# Bus_V3_1.net
KiCad netlist of a schematic drawn in EAGLE
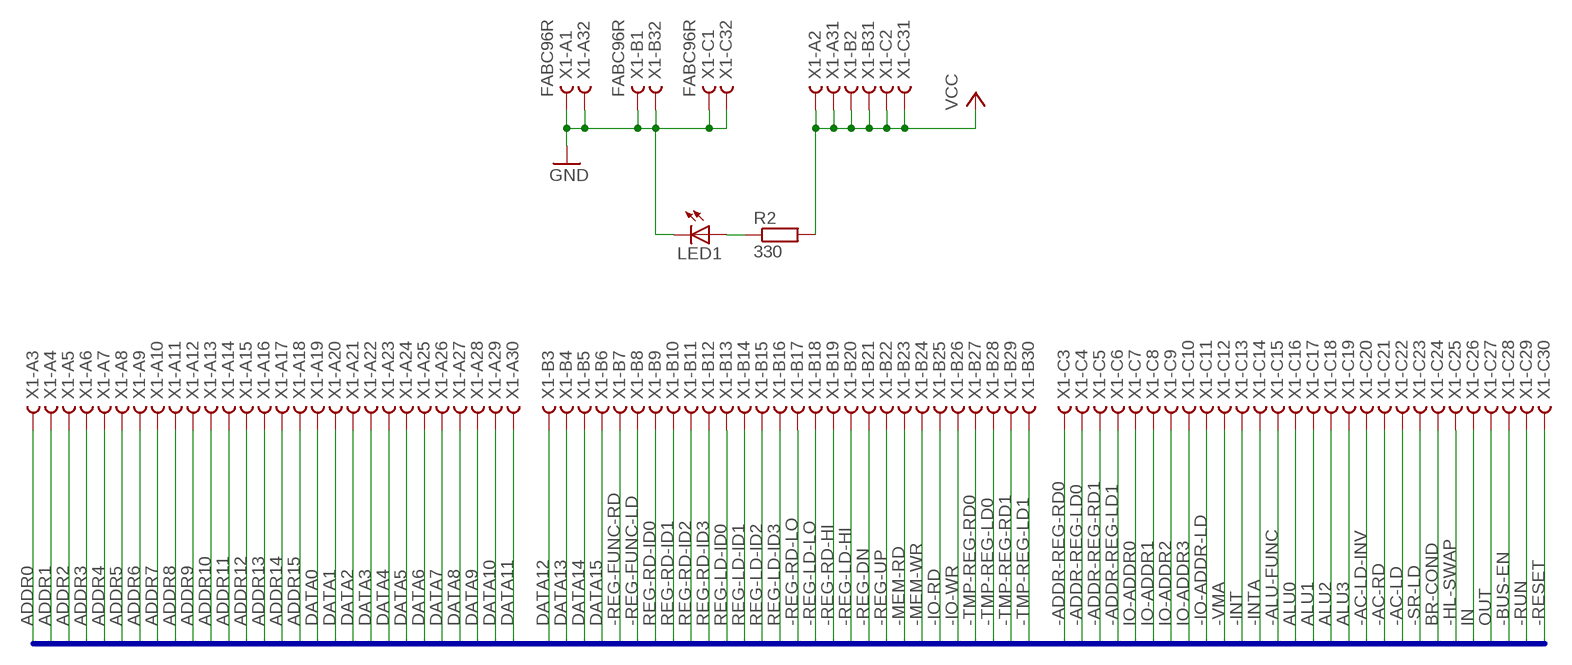
[diagram p0: schematic, sheet 1]

(export (version "E")
  (design (tool "Eeschema 10.0.6"))
  (components
    (comp (ref "LED1")
      (value "LED5MM")
      (footprint "eagle-import:LED5MM")
      (libsource (lib "eagle-import") (part "LED5MM"))
    )
    (comp (ref "R2")
      (value "330")
      (footprint "eagle-import:0207_10")
      (libsource (lib "eagle-import") (part "R0207/10"))
    )
    (comp (ref "X1")
      (value "FABC96R")
      (footprint "eagle-import:FABC96R")
      (libsource (lib "eagle-import") (part "FABC96R"))
    )
  )
  (nets
    (net (code "1") (name "/-AC-LD") (class "Default")
      (node (ref "X1") (pin "C22") (pinfunction "B_C22") (pintype "passive"))
    )
    (net (code "2") (name "/-AC-LD-INV") (class "Default")
      (node (ref "X1") (pin "C20") (pinfunction "B_C20") (pintype "passive"))
    )
    (net (code "3") (name "/-AC-RD") (class "Default")
      (node (ref "X1") (pin "C21") (pinfunction "B_C21") (pintype "passive"))
    )
    (net (code "4") (name "/-ADDR-REG-LD0") (class "Default")
      (node (ref "X1") (pin "C4") (pinfunction "B_C4") (pintype "passive"))
    )
    (net (code "5") (name "/-ADDR-REG-LD1") (class "Default")
      (node (ref "X1") (pin "C6") (pinfunction "B_C6") (pintype "passive"))
    )
    (net (code "6") (name "/-ADDR-REG-RD0") (class "Default")
      (node (ref "X1") (pin "C3") (pinfunction "B_C3") (pintype "passive"))
    )
    (net (code "7") (name "/-ADDR-REG-RD1") (class "Default")
      (node (ref "X1") (pin "C5") (pinfunction "B_C5") (pintype "passive"))
    )
    (net (code "8") (name "/-ALU-FUNC") (class "Default")
      (node (ref "X1") (pin "C15") (pinfunction "B_C15") (pintype "passive"))
    )
    (net (code "9") (name "/-BUS-EN") (class "Default")
      (node (ref "X1") (pin "C28") (pinfunction "B_C28") (pintype "passive"))
    )
    (net (code "10") (name "/-HL-SWAP") (class "Default")
      (node (ref "X1") (pin "C25") (pinfunction "B_C25") (pintype "passive"))
    )
    (net (code "11") (name "/-INT") (class "Default")
      (node (ref "X1") (pin "C13") (pinfunction "B_C13") (pintype "passive"))
    )
    (net (code "12") (name "/-INTA") (class "Default")
      (node (ref "X1") (pin "C14") (pinfunction "B_C14") (pintype "passive"))
    )
    (net (code "13") (name "/-IO-ADDR-LD") (class "Default")
      (node (ref "X1") (pin "C11") (pinfunction "B_C11") (pintype "passive"))
    )
    (net (code "14") (name "/-IO-RD") (class "Default")
      (node (ref "X1") (pin "B25") (pinfunction "B_B25") (pintype "passive"))
    )
    (net (code "15") (name "/-IO-WR") (class "Default")
      (node (ref "X1") (pin "B26") (pinfunction "B_B26") (pintype "passive"))
    )
    (net (code "16") (name "/-MEM-RD") (class "Default")
      (node (ref "X1") (pin "B23") (pinfunction "B_B23") (pintype "passive"))
    )
    (net (code "17") (name "/-MEM-WR") (class "Default")
      (node (ref "X1") (pin "B24") (pinfunction "B_B24") (pintype "passive"))
    )
    (net (code "18") (name "/-REG-DN") (class "Default")
      (node (ref "X1") (pin "B21") (pinfunction "B_B21") (pintype "passive"))
    )
    (net (code "19") (name "/-REG-FUNC-LD") (class "Default")
      (node (ref "X1") (pin "B8") (pinfunction "B_B8") (pintype "passive"))
    )
    (net (code "20") (name "/-REG-FUNC-RD") (class "Default")
      (node (ref "X1") (pin "B7") (pinfunction "B_B7") (pintype "passive"))
    )
    (net (code "21") (name "/-REG-LD-HI") (class "Default")
      (node (ref "X1") (pin "B20") (pinfunction "B_B20") (pintype "passive"))
    )
    (net (code "22") (name "/-REG-LD-LO") (class "Default")
      (node (ref "X1") (pin "B18") (pinfunction "B_B18") (pintype "passive"))
    )
    (net (code "23") (name "/-REG-RD-HI") (class "Default")
      (node (ref "X1") (pin "B19") (pinfunction "B_B19") (pintype "passive"))
    )
    (net (code "24") (name "/-REG-RD-LO") (class "Default")
      (node (ref "X1") (pin "B17") (pinfunction "B_B17") (pintype "passive"))
    )
    (net (code "25") (name "/-REG-UP") (class "Default")
      (node (ref "X1") (pin "B22") (pinfunction "B_B22") (pintype "passive"))
    )
    (net (code "26") (name "/-RESET") (class "Default")
      (node (ref "X1") (pin "C30") (pinfunction "B_C30") (pintype "passive"))
    )
    (net (code "27") (name "/-RUN") (class "Default")
      (node (ref "X1") (pin "C29") (pinfunction "B_C29") (pintype "passive"))
    )
    (net (code "28") (name "/-SR-LD") (class "Default")
      (node (ref "X1") (pin "C23") (pinfunction "B_C23") (pintype "passive"))
    )
    (net (code "29") (name "/-TMP-REG-LD0") (class "Default")
      (node (ref "X1") (pin "B28") (pinfunction "B_B28") (pintype "passive"))
    )
    (net (code "30") (name "/-TMP-REG-LD1") (class "Default")
      (node (ref "X1") (pin "B30") (pinfunction "B_B30") (pintype "passive"))
    )
    (net (code "31") (name "/-TMP-REG-RD0") (class "Default")
      (node (ref "X1") (pin "B27") (pinfunction "B_B27") (pintype "passive"))
    )
    (net (code "32") (name "/-TMP-REG-RD1") (class "Default")
      (node (ref "X1") (pin "B29") (pinfunction "B_B29") (pintype "passive"))
    )
    (net (code "33") (name "/-VMA") (class "Default")
      (node (ref "X1") (pin "C12") (pinfunction "B_C12") (pintype "passive"))
    )
    (net (code "34") (name "/ADDR0") (class "Default")
      (node (ref "X1") (pin "A3") (pinfunction "B_A3") (pintype "passive"))
    )
    (net (code "35") (name "/ADDR1") (class "Default")
      (node (ref "X1") (pin "A4") (pinfunction "B_A4") (pintype "passive"))
    )
    (net (code "36") (name "/ADDR2") (class "Default")
      (node (ref "X1") (pin "A5") (pinfunction "B_A5") (pintype "passive"))
    )
    (net (code "37") (name "/ADDR3") (class "Default")
      (node (ref "X1") (pin "A6") (pinfunction "B_A6") (pintype "passive"))
    )
    (net (code "38") (name "/ADDR4") (class "Default")
      (node (ref "X1") (pin "A7") (pinfunction "B_A7") (pintype "passive"))
    )
    (net (code "39") (name "/ADDR5") (class "Default")
      (node (ref "X1") (pin "A8") (pinfunction "B_A8") (pintype "passive"))
    )
    (net (code "40") (name "/ADDR6") (class "Default")
      (node (ref "X1") (pin "A9") (pinfunction "B_A9") (pintype "passive"))
    )
    (net (code "41") (name "/ADDR7") (class "Default")
      (node (ref "X1") (pin "A10") (pinfunction "B_A10") (pintype "passive"))
    )
    (net (code "42") (name "/ADDR8") (class "Default")
      (node (ref "X1") (pin "A11") (pinfunction "B_A11") (pintype "passive"))
    )
    (net (code "43") (name "/ADDR9") (class "Default")
      (node (ref "X1") (pin "A12") (pinfunction "B_A12") (pintype "passive"))
    )
    (net (code "44") (name "/ADDR10") (class "Default")
      (node (ref "X1") (pin "A13") (pinfunction "B_A13") (pintype "passive"))
    )
    (net (code "45") (name "/ADDR11") (class "Default")
      (node (ref "X1") (pin "A14") (pinfunction "B_A14") (pintype "passive"))
    )
    (net (code "46") (name "/ADDR12") (class "Default")
      (node (ref "X1") (pin "A15") (pinfunction "B_A15") (pintype "passive"))
    )
    (net (code "47") (name "/ADDR13") (class "Default")
      (node (ref "X1") (pin "A16") (pinfunction "B_A16") (pintype "passive"))
    )
    (net (code "48") (name "/ADDR14") (class "Default")
      (node (ref "X1") (pin "A17") (pinfunction "B_A17") (pintype "passive"))
    )
    (net (code "49") (name "/ADDR15") (class "Default")
      (node (ref "X1") (pin "A18") (pinfunction "B_A18") (pintype "passive"))
    )
    (net (code "50") (name "/ALU0") (class "Default")
      (node (ref "X1") (pin "C16") (pinfunction "B_C16") (pintype "passive"))
    )
    (net (code "51") (name "/ALU1") (class "Default")
      (node (ref "X1") (pin "C17") (pinfunction "B_C17") (pintype "passive"))
    )
    (net (code "52") (name "/ALU2") (class "Default")
      (node (ref "X1") (pin "C18") (pinfunction "B_C18") (pintype "passive"))
    )
    (net (code "53") (name "/ALU3") (class "Default")
      (node (ref "X1") (pin "C19") (pinfunction "B_C19") (pintype "passive"))
    )
    (net (code "54") (name "/BR-COND") (class "Default")
      (node (ref "X1") (pin "C24") (pinfunction "B_C24") (pintype "passive"))
    )
    (net (code "55") (name "/DATA0") (class "Default")
      (node (ref "X1") (pin "A19") (pinfunction "B_A19") (pintype "passive"))
    )
    (net (code "56") (name "/DATA1") (class "Default")
      (node (ref "X1") (pin "A20") (pinfunction "B_A20") (pintype "passive"))
    )
    (net (code "57") (name "/DATA2") (class "Default")
      (node (ref "X1") (pin "A21") (pinfunction "B_A21") (pintype "passive"))
    )
    (net (code "58") (name "/DATA3") (class "Default")
      (node (ref "X1") (pin "A22") (pinfunction "B_A22") (pintype "passive"))
    )
    (net (code "59") (name "/DATA4") (class "Default")
      (node (ref "X1") (pin "A23") (pinfunction "B_A23") (pintype "passive"))
    )
    (net (code "60") (name "/DATA5") (class "Default")
      (node (ref "X1") (pin "A24") (pinfunction "B_A24") (pintype "passive"))
    )
    (net (code "61") (name "/DATA6") (class "Default")
      (node (ref "X1") (pin "A25") (pinfunction "B_A25") (pintype "passive"))
    )
    (net (code "62") (name "/DATA7") (class "Default")
      (node (ref "X1") (pin "A26") (pinfunction "B_A26") (pintype "passive"))
    )
    (net (code "63") (name "/DATA8") (class "Default")
      (node (ref "X1") (pin "A27") (pinfunction "B_A27") (pintype "passive"))
    )
    (net (code "64") (name "/DATA9") (class "Default")
      (node (ref "X1") (pin "A28") (pinfunction "B_A28") (pintype "passive"))
    )
    (net (code "65") (name "/DATA10") (class "Default")
      (node (ref "X1") (pin "A29") (pinfunction "B_A29") (pintype "passive"))
    )
    (net (code "66") (name "/DATA11") (class "Default")
      (node (ref "X1") (pin "A30") (pinfunction "B_A30") (pintype "passive"))
    )
    (net (code "67") (name "/DATA12") (class "Default")
      (node (ref "X1") (pin "B3") (pinfunction "B_B3") (pintype "passive"))
    )
    (net (code "68") (name "/DATA13") (class "Default")
      (node (ref "X1") (pin "B4") (pinfunction "B_B4") (pintype "passive"))
    )
    (net (code "69") (name "/DATA14") (class "Default")
      (node (ref "X1") (pin "B5") (pinfunction "B_B5") (pintype "passive"))
    )
    (net (code "70") (name "/DATA15") (class "Default")
      (node (ref "X1") (pin "B6") (pinfunction "B_B6") (pintype "passive"))
    )
    (net (code "71") (name "/IN") (class "Default")
      (node (ref "X1") (pin "C26") (pinfunction "B_C26") (pintype "passive"))
    )
    (net (code "72") (name "/IO-ADDR0") (class "Default")
      (node (ref "X1") (pin "C7") (pinfunction "B_C7") (pintype "passive"))
    )
    (net (code "73") (name "/IO-ADDR1") (class "Default")
      (node (ref "X1") (pin "C8") (pinfunction "B_C8") (pintype "passive"))
    )
    (net (code "74") (name "/IO-ADDR2") (class "Default")
      (node (ref "X1") (pin "C9") (pinfunction "B_C9") (pintype "passive"))
    )
    (net (code "75") (name "/IO-ADDR3") (class "Default")
      (node (ref "X1") (pin "C10") (pinfunction "B_C10") (pintype "passive"))
    )
    (net (code "76") (name "/OUT") (class "Default")
      (node (ref "X1") (pin "C27") (pinfunction "B_C27") (pintype "passive"))
    )
    (net (code "77") (name "/REG-LD-ID0") (class "Default")
      (node (ref "X1") (pin "B13") (pinfunction "B_B13") (pintype "passive"))
    )
    (net (code "78") (name "/REG-LD-ID1") (class "Default")
      (node (ref "X1") (pin "B14") (pinfunction "B_B14") (pintype "passive"))
    )
    (net (code "79") (name "/REG-LD-ID2") (class "Default")
      (node (ref "X1") (pin "B15") (pinfunction "B_B15") (pintype "passive"))
    )
    (net (code "80") (name "/REG-LD-ID3") (class "Default")
      (node (ref "X1") (pin "B16") (pinfunction "B_B16") (pintype "passive"))
    )
    (net (code "81") (name "/REG-RD-ID0") (class "Default")
      (node (ref "X1") (pin "B9") (pinfunction "B_B9") (pintype "passive"))
    )
    (net (code "82") (name "/REG-RD-ID1") (class "Default")
      (node (ref "X1") (pin "B10") (pinfunction "B_B10") (pintype "passive"))
    )
    (net (code "83") (name "/REG-RD-ID2") (class "Default")
      (node (ref "X1") (pin "B11") (pinfunction "B_B11") (pintype "passive"))
    )
    (net (code "84") (name "/REG-RD-ID3") (class "Default")
      (node (ref "X1") (pin "B12") (pinfunction "B_B12") (pintype "passive"))
    )
    (net (code "85") (name "GND") (class "Default")
      (node (ref "LED1") (pin "K") (pinfunction "C_K") (pintype "passive"))
      (node (ref "X1") (pin "A1") (pinfunction "B_A1") (pintype "passive"))
      (node (ref "X1") (pin "A32") (pinfunction "B_A32") (pintype "passive"))
      (node (ref "X1") (pin "B1") (pinfunction "B_B1") (pintype "passive"))
      (node (ref "X1") (pin "B32") (pinfunction "B_B32") (pintype "passive"))
      (node (ref "X1") (pin "C1") (pinfunction "B_C1") (pintype "passive"))
      (node (ref "X1") (pin "C32") (pinfunction "B_C32") (pintype "passive"))
    )
    (net (code "86") (name "Net-(LED1-PadA)") (class "Default")
      (node (ref "LED1") (pin "A") (pinfunction "A_A") (pintype "passive"))
      (node (ref "R2") (pin "1") (pinfunction "1_1") (pintype "passive"))
    )
    (net (code "87") (name "VCC") (class "Default")
      (node (ref "R2") (pin "2") (pinfunction "2_2") (pintype "passive"))
      (node (ref "X1") (pin "A2") (pinfunction "B_A2") (pintype "passive"))
      (node (ref "X1") (pin "A31") (pinfunction "B_A31") (pintype "passive"))
      (node (ref "X1") (pin "B2") (pinfunction "B_B2") (pintype "passive"))
      (node (ref "X1") (pin "B31") (pinfunction "B_B31") (pintype "passive"))
      (node (ref "X1") (pin "C2") (pinfunction "B_C2") (pintype "passive"))
      (node (ref "X1") (pin "C31") (pinfunction "B_C31") (pintype "passive"))
    )
  )
)
